# LB_BIT_i1_SLIDESWITCH-v03_rev2.net
KiCad netlist of a schematic drawn in EAGLE
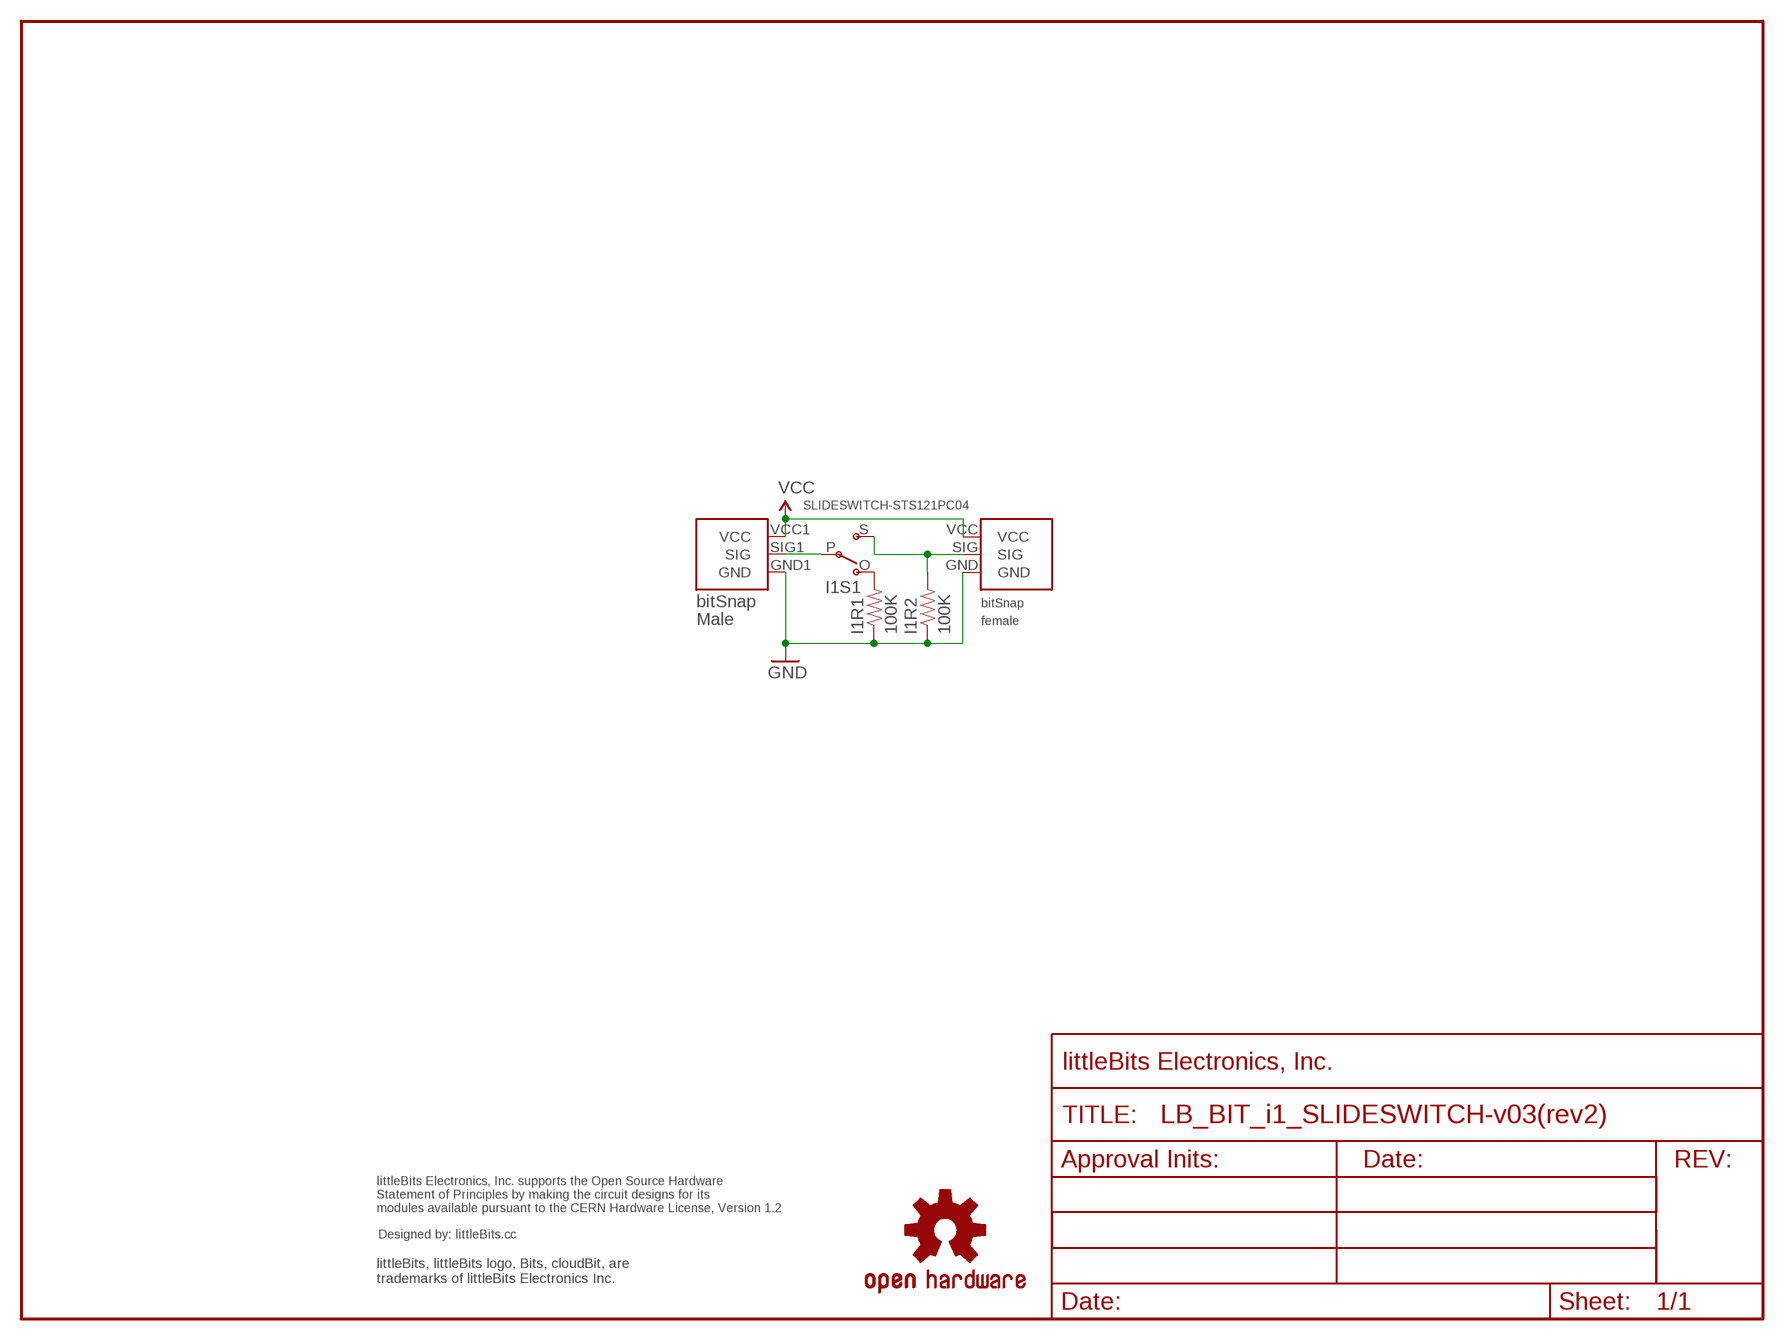
[diagram p0: schematic, sheet 1]

(export (version "E")
  (design (tool "Eeschema 10.0.6"))
  (components
    (comp (ref "I1BSF1")
      (value "BITSNAP_V03_FEMALE")
      (footprint "eagle-import:BITSNAP_V03_FEMALE")
      (libsource (lib "eagle-import") (part "BITSNAP_V03_FEMALE"))
    )
    (comp (ref "I1BSM1")
      (value "BITSNAP_V03_MALE")
      (footprint "eagle-import:BITSNAP_V03_MALE")
      (libsource (lib "eagle-import") (part "BITSNAP_V03_MALE"))
    )
    (comp (ref "I1R1")
      (value "100K")
      (footprint "eagle-import:0603-RES")
      (libsource (lib "eagle-import") (part "RESISTOR0603-RES"))
    )
    (comp (ref "I1R2")
      (value "100K")
      (footprint "eagle-import:0603-RES")
      (libsource (lib "eagle-import") (part "RESISTOR0603-RES"))
    )
    (comp (ref "I1S1")
      (value "SLIDESWITCH-STS121PC04")
      (footprint "eagle-import:SLIDESWITCH-STS121PC04")
      (libsource (lib "eagle-import") (part "SLIDESWITCH-STS121PC04"))
    )
    (comp (ref "U$1")
      (value "OSHW-LOGOL")
      (footprint "eagle-import:OSHW-LOGO-L")
      (libsource (lib "eagle-import") (part "OSHW-LOGOL"))
    )
    (comp (ref "U$2")
      (value "FRAME-LETTER-OHWOHW")
      (footprint "eagle-import:FABDWG01-OHW")
      (libsource (lib "eagle-import") (part "FRAME-LETTER-OHWOHW"))
    )
    (comp (ref "U$3")
      (value "LB_CREDITS")
      (footprint "eagle-import:OSHWCREDIT")
      (libsource (lib "eagle-import") (part "LB_CREDITS"))
    )
  )
  (nets
    (net (code "1") (name "GND") (class "Default")
      (node (ref "I1BSF1") (pin "GND") (pinfunction "GND_GND") (pintype "bidirectional"))
      (node (ref "I1BSM1") (pin "GND1") (pinfunction "GND_GND1") (pintype "bidirectional"))
      (node (ref "I1R1") (pin "1") (pinfunction "1_1") (pintype "passive"))
      (node (ref "I1R2") (pin "1") (pinfunction "1_1") (pintype "passive"))
    )
    (net (code "2") (name "Net-(I1BSF1-PadSIG)") (class "Default")
      (node (ref "I1BSF1") (pin "SIG") (pinfunction "SIG_SIG") (pintype "bidirectional"))
      (node (ref "I1R2") (pin "2") (pinfunction "2_2") (pintype "passive"))
      (node (ref "I1S1") (pin "S") (pinfunction "S_S") (pintype "passive"))
    )
    (net (code "3") (name "Net-(I1BSM1-SIG)") (class "Default")
      (node (ref "I1BSM1") (pin "SIG1") (pinfunction "SIG_SIG1") (pintype "bidirectional"))
      (node (ref "I1S1") (pin "P") (pinfunction "P_P") (pintype "passive"))
    )
    (net (code "4") (name "Net-(I1R1-Pad2)") (class "Default")
      (node (ref "I1R1") (pin "2") (pinfunction "2_2") (pintype "passive"))
      (node (ref "I1S1") (pin "O") (pinfunction "O_O") (pintype "passive"))
    )
    (net (code "5") (name "VCC") (class "Default")
      (node (ref "I1BSF1") (pin "VCC") (pinfunction "VCC_VCC") (pintype "bidirectional"))
      (node (ref "I1BSM1") (pin "VCC1") (pinfunction "VCC_VCC1") (pintype "bidirectional"))
    )
  )
)
